# 8.net
KiCad netlist of a schematic drawn in Altium Designer
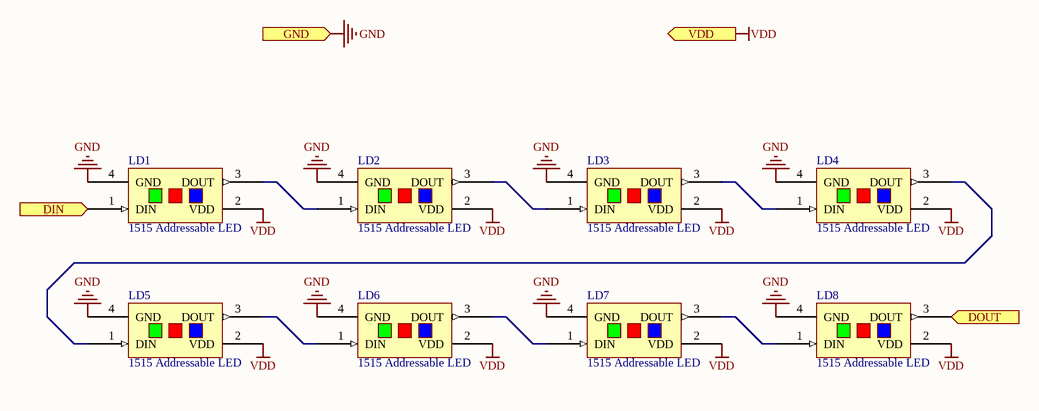
[diagram p0: 8.SchDoc]

(export (version "E")
  (design (tool "Eeschema 10.0.6"))
  (components
    (comp (ref "LD1")
      (value "1515 Addressable LED")
      (footprint "SK6805-EC 15 DENSE")
      (libsource (lib "SchmittLib") (part "SK6805-EC 15"))
    )
    (comp (ref "LD2")
      (value "1515 Addressable LED")
      (footprint "SK6805-EC 15 DENSE")
      (libsource (lib "SchmittLib") (part "SK6805-EC 15"))
    )
    (comp (ref "LD3")
      (value "1515 Addressable LED")
      (footprint "SK6805-EC 15 DENSE")
      (libsource (lib "SchmittLib") (part "SK6805-EC 15"))
    )
    (comp (ref "LD4")
      (value "1515 Addressable LED")
      (footprint "SK6805-EC 15 DENSE")
      (libsource (lib "SchmittLib") (part "SK6805-EC 15"))
    )
    (comp (ref "LD5")
      (value "1515 Addressable LED")
      (footprint "SK6805-EC 15 DENSE")
      (libsource (lib "SchmittLib") (part "SK6805-EC 15"))
    )
    (comp (ref "LD6")
      (value "1515 Addressable LED")
      (footprint "SK6805-EC 15 DENSE")
      (libsource (lib "SchmittLib") (part "SK6805-EC 15"))
    )
    (comp (ref "LD7")
      (value "1515 Addressable LED")
      (footprint "SK6805-EC 15 DENSE")
      (libsource (lib "SchmittLib") (part "SK6805-EC 15"))
    )
    (comp (ref "LD8")
      (value "1515 Addressable LED")
      (footprint "SK6805-EC 15 DENSE")
      (libsource (lib "SchmittLib") (part "SK6805-EC 15"))
    )
  )
  (nets
    (net (code "1") (name "/DIN") (class "Default")
      (node (ref "LD1") (pin "1") (pinfunction "DIN_1") (pintype "input"))
    )
    (net (code "2") (name "/DOUT") (class "Default")
      (node (ref "LD8") (pin "3") (pinfunction "DOUT_3") (pintype "output"))
    )
    (net (code "3") (name "GND") (class "Default")
      (node (ref "LD1") (pin "4") (pinfunction "GND_4") (pintype "power_in"))
      (node (ref "LD2") (pin "4") (pinfunction "GND_4") (pintype "power_in"))
      (node (ref "LD3") (pin "4") (pinfunction "GND_4") (pintype "power_in"))
      (node (ref "LD4") (pin "4") (pinfunction "GND_4") (pintype "power_in"))
      (node (ref "LD5") (pin "4") (pinfunction "GND_4") (pintype "power_in"))
      (node (ref "LD6") (pin "4") (pinfunction "GND_4") (pintype "power_in"))
      (node (ref "LD7") (pin "4") (pinfunction "GND_4") (pintype "power_in"))
      (node (ref "LD8") (pin "4") (pinfunction "GND_4") (pintype "power_in"))
    )
    (net (code "4") (name "Net-(LD1-DOUT)") (class "Default")
      (node (ref "LD1") (pin "3") (pinfunction "DOUT_3") (pintype "output"))
      (node (ref "LD2") (pin "1") (pinfunction "DIN_1") (pintype "input"))
    )
    (net (code "5") (name "Net-(LD2-DOUT)") (class "Default")
      (node (ref "LD2") (pin "3") (pinfunction "DOUT_3") (pintype "output"))
      (node (ref "LD3") (pin "1") (pinfunction "DIN_1") (pintype "input"))
    )
    (net (code "6") (name "Net-(LD3-DOUT)") (class "Default")
      (node (ref "LD3") (pin "3") (pinfunction "DOUT_3") (pintype "output"))
      (node (ref "LD4") (pin "1") (pinfunction "DIN_1") (pintype "input"))
    )
    (net (code "7") (name "Net-(LD4-DOUT)") (class "Default")
      (node (ref "LD4") (pin "3") (pinfunction "DOUT_3") (pintype "output"))
      (node (ref "LD5") (pin "1") (pinfunction "DIN_1") (pintype "input"))
    )
    (net (code "8") (name "Net-(LD5-DOUT)") (class "Default")
      (node (ref "LD5") (pin "3") (pinfunction "DOUT_3") (pintype "output"))
      (node (ref "LD6") (pin "1") (pinfunction "DIN_1") (pintype "input"))
    )
    (net (code "9") (name "Net-(LD6-DOUT)") (class "Default")
      (node (ref "LD6") (pin "3") (pinfunction "DOUT_3") (pintype "output"))
      (node (ref "LD7") (pin "1") (pinfunction "DIN_1") (pintype "input"))
    )
    (net (code "10") (name "Net-(LD7-DOUT)") (class "Default")
      (node (ref "LD7") (pin "3") (pinfunction "DOUT_3") (pintype "output"))
      (node (ref "LD8") (pin "1") (pinfunction "DIN_1") (pintype "input"))
    )
    (net (code "11") (name "VDD") (class "Default")
      (node (ref "LD1") (pin "2") (pinfunction "VDD_2") (pintype "power_in"))
      (node (ref "LD2") (pin "2") (pinfunction "VDD_2") (pintype "power_in"))
      (node (ref "LD3") (pin "2") (pinfunction "VDD_2") (pintype "power_in"))
      (node (ref "LD4") (pin "2") (pinfunction "VDD_2") (pintype "power_in"))
      (node (ref "LD5") (pin "2") (pinfunction "VDD_2") (pintype "power_in"))
      (node (ref "LD6") (pin "2") (pinfunction "VDD_2") (pintype "power_in"))
      (node (ref "LD7") (pin "2") (pinfunction "VDD_2") (pintype "power_in"))
      (node (ref "LD8") (pin "2") (pinfunction "VDD_2") (pintype "power_in"))
    )
  )
)
